# board.net
KiCad netlist of a schematic drawn in EAGLE
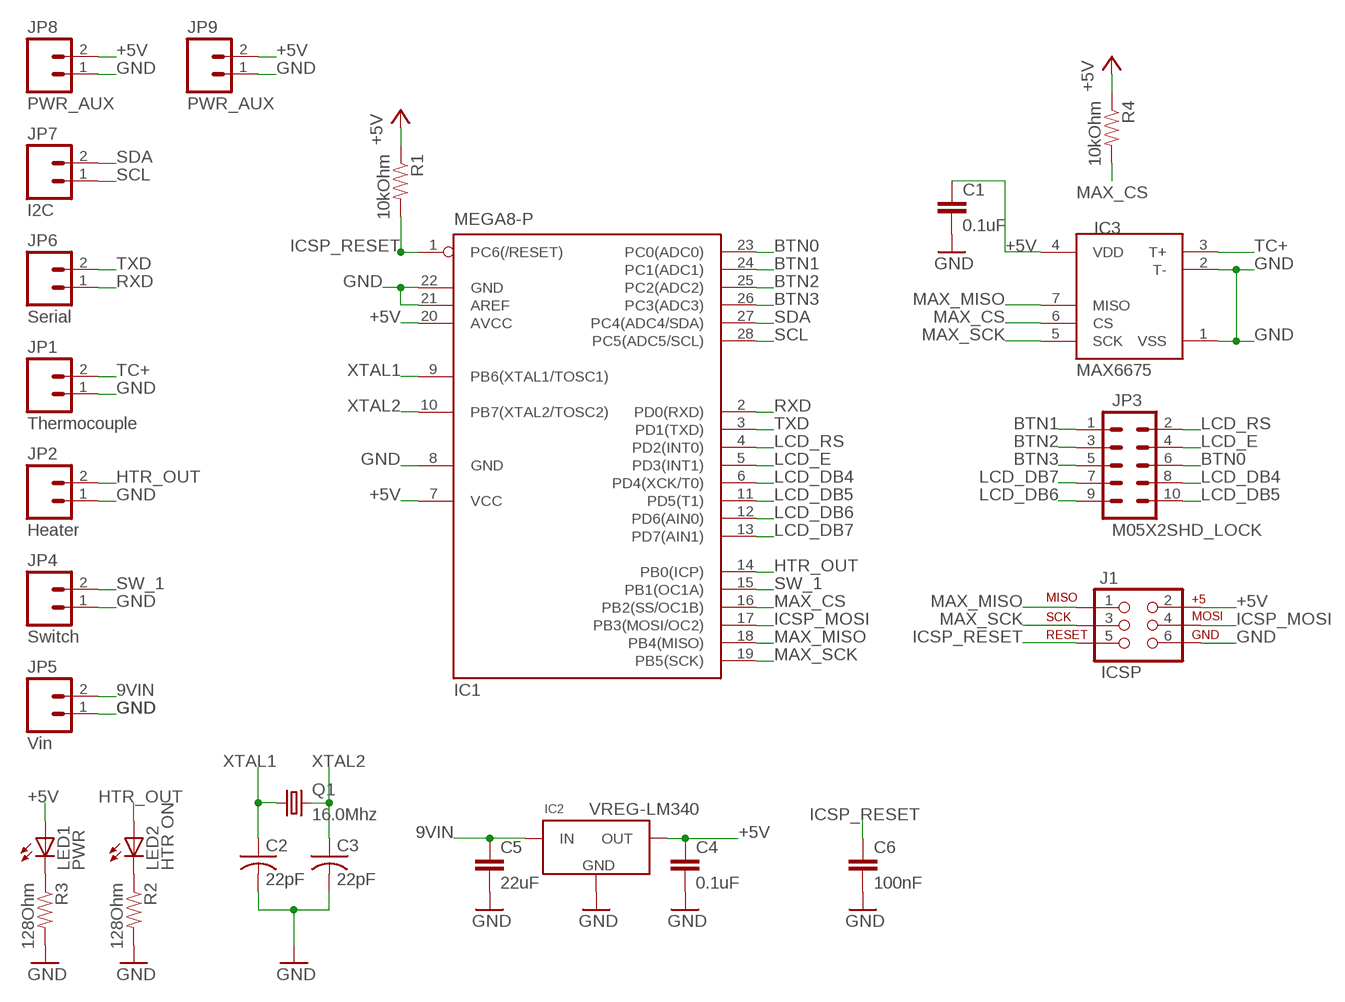
[diagram p0: schematic, sheet 1]

(export (version "E")
  (design (tool "Eeschema 10.0.6"))
  (components
    (comp (ref "C1")
      (value "0.1uF")
      (footprint "eagle-import:CAP-PTH-SMALL")
      (libsource (lib "eagle-import") (part "SparkFun-Passives_CAPPTH"))
    )
    (comp (ref "C2")
      (value "22pF")
      (footprint "eagle-import:C025-030X050")
      (libsource (lib "eagle-import") (part "C-US025-030X050"))
    )
    (comp (ref "C3")
      (value "22pF")
      (footprint "eagle-import:C025-030X050")
      (libsource (lib "eagle-import") (part "C-US025-030X050"))
    )
    (comp (ref "C4")
      (value "0.1uF")
      (footprint "eagle-import:CAP-PTH-SMALL")
      (libsource (lib "eagle-import") (part "SparkFun-Passives_CAPPTH"))
    )
    (comp (ref "C5")
      (value "22uF")
      (footprint "eagle-import:CAP-PTH-5MM")
      (libsource (lib "eagle-import") (part "CAPPTH1"))
    )
    (comp (ref "C6")
      (value "100nF")
      (footprint "eagle-import:0603-CAP")
      (libsource (lib "eagle-import") (part "CAP0603-CAP"))
    )
    (comp (ref "IC1")
      (value "MEGA8-P")
      (footprint "eagle-import:DIL28-3")
      (libsource (lib "eagle-import") (part "MEGA8-P"))
    )
    (comp (ref "IC2")
      (value "VREG-LM340")
      (footprint "eagle-import:D2PACK_A")
      (libsource (lib "eagle-import") (part "VREG-LM340"))
    )
    (comp (ref "IC3")
      (value "MAX6675")
      (footprint "eagle-import:SO08-MAX6675")
      (libsource (lib "eagle-import") (part "MAX6675"))
    )
    (comp (ref "J1")
      (value "ICSP")
      (footprint "eagle-import:2X3")
      (libsource (lib "eagle-import") (part "AVR_SPI_PRG_6PTH"))
    )
    (comp (ref "JP1")
      (value "Thermocouple")
      (footprint "eagle-import:SCREWTERMINAL-5MM-2")
      (libsource (lib "eagle-import") (part "M025MM"))
    )
    (comp (ref "JP2")
      (value "Heater")
      (footprint "eagle-import:SCREWTERMINAL-5MM-2")
      (libsource (lib "eagle-import") (part "M025MM"))
    )
    (comp (ref "JP3")
      (value "M05X2SHD_LOCK")
      (footprint "eagle-import:2X5-SHROUDED_LOCK")
      (libsource (lib "eagle-import") (part "M05X2SHD_LOCK"))
    )
    (comp (ref "JP4")
      (value "Switch")
      (footprint "eagle-import:SCREWTERMINAL-5MM-2")
      (libsource (lib "eagle-import") (part "M025MM"))
    )
    (comp (ref "JP5")
      (value "Vin")
      (footprint "eagle-import:SCREWTERMINAL-5MM-2")
      (libsource (lib "eagle-import") (part "M025MM"))
    )
    (comp (ref "JP6")
      (value "Serial")
      (footprint "eagle-import:1X02")
      (libsource (lib "eagle-import") (part "M02PTH"))
    )
    (comp (ref "JP7")
      (value "I2C")
      (footprint "eagle-import:1X02")
      (libsource (lib "eagle-import") (part "M02PTH"))
    )
    (comp (ref "JP8")
      (value "PWR_AUX")
      (footprint "eagle-import:1X02")
      (libsource (lib "eagle-import") (part "M02PTH"))
    )
    (comp (ref "JP9")
      (value "PWR_AUX")
      (footprint "eagle-import:1X02")
      (libsource (lib "eagle-import") (part "M02PTH"))
    )
    (comp (ref "LED1")
      (value "PWR")
      (footprint "eagle-import:LED-0603")
      (libsource (lib "eagle-import") (part "LED-GREEN0603"))
    )
    (comp (ref "LED2")
      (value "HTR ON")
      (footprint "eagle-import:LED-0603")
      (fields (field (name "PROD_ID") "DIO-00819"))
      (libsource (lib "eagle-import") (part "LED-RED0603"))
    )
    (comp (ref "Q1")
      (value "16.0Mhz")
      (footprint "eagle-import:HC49_S")
      (libsource (lib "eagle-import") (part "CRYSTALHC49S"))
    )
    (comp (ref "R1")
      (value "10kOhm")
      (footprint "eagle-import:1206")
      (libsource (lib "eagle-import") (part "RESISTOR1206"))
    )
    (comp (ref "R2")
      (value "128Ohm")
      (footprint "eagle-import:1206")
      (libsource (lib "eagle-import") (part "RESISTOR1206"))
    )
    (comp (ref "R3")
      (value "128Ohm")
      (footprint "eagle-import:1206")
      (libsource (lib "eagle-import") (part "RESISTOR1206"))
    )
    (comp (ref "R4")
      (value "10kOhm")
      (footprint "eagle-import:1206")
      (libsource (lib "eagle-import") (part "RESISTOR1206"))
    )
  )
  (nets
    (net (code "1") (name "+5V") (class "Default")
      (node (ref "C1") (pin "1") (pinfunction "1_1") (pintype "passive"))
      (node (ref "C4") (pin "1") (pinfunction "1_1") (pintype "passive"))
      (node (ref "IC1") (pin "20") (pinfunction "AVCC_20") (pintype "power_in"))
      (node (ref "IC1") (pin "7") (pinfunction "VCC_7") (pintype "power_in"))
      (node (ref "IC2") (pin "3") (pinfunction "OUT_3") (pintype "bidirectional"))
      (node (ref "IC3") (pin "4") (pinfunction "VDD_4") (pintype "bidirectional"))
      (node (ref "J1") (pin "2") (pinfunction "2_2") (pintype "passive"))
      (node (ref "JP8") (pin "2") (pinfunction "2_2") (pintype "passive"))
      (node (ref "JP9") (pin "2") (pinfunction "2_2") (pintype "passive"))
      (node (ref "LED1") (pin "A") (pinfunction "A_A") (pintype "passive"))
      (node (ref "R1") (pin "1") (pinfunction "1_1") (pintype "passive"))
      (node (ref "R4") (pin "1") (pinfunction "1_1") (pintype "passive"))
    )
    (net (code "2") (name "/9VIN") (class "Default")
      (node (ref "C5") (pin "1") (pinfunction "1_1") (pintype "passive"))
      (node (ref "IC2") (pin "1") (pinfunction "IN_1") (pintype "bidirectional"))
      (node (ref "JP5") (pin "2") (pinfunction "2_2") (pintype "passive"))
    )
    (net (code "3") (name "/BTN0") (class "Default")
      (node (ref "IC1") (pin "23") (pinfunction "PC0(ADC0)_23") (pintype "bidirectional"))
      (node (ref "JP3") (pin "6") (pinfunction "6_6") (pintype "passive"))
    )
    (net (code "4") (name "/BTN1") (class "Default")
      (node (ref "IC1") (pin "24") (pinfunction "PC1(ADC1)_24") (pintype "bidirectional"))
      (node (ref "JP3") (pin "1") (pinfunction "1_1") (pintype "passive"))
    )
    (net (code "5") (name "/BTN2") (class "Default")
      (node (ref "IC1") (pin "25") (pinfunction "PC2(ADC2)_25") (pintype "bidirectional"))
      (node (ref "JP3") (pin "3") (pinfunction "3_3") (pintype "passive"))
    )
    (net (code "6") (name "/BTN3") (class "Default")
      (node (ref "IC1") (pin "26") (pinfunction "PC3(ADC3)_26") (pintype "bidirectional"))
      (node (ref "JP3") (pin "5") (pinfunction "5_5") (pintype "passive"))
    )
    (net (code "7") (name "/HTR_OUT") (class "Default")
      (node (ref "IC1") (pin "14") (pinfunction "PB0(ICP)_14") (pintype "bidirectional"))
      (node (ref "JP2") (pin "2") (pinfunction "2_2") (pintype "passive"))
      (node (ref "LED2") (pin "A") (pinfunction "A_A") (pintype "passive"))
    )
    (net (code "8") (name "/ICSP_MOSI") (class "Default")
      (node (ref "IC1") (pin "17") (pinfunction "PB3(MOSI/OC2)_17") (pintype "bidirectional"))
      (node (ref "J1") (pin "4") (pinfunction "4_4") (pintype "passive"))
    )
    (net (code "9") (name "/ICSP_RESET") (class "Default")
      (node (ref "C6") (pin "1") (pinfunction "1_1") (pintype "passive"))
      (node (ref "IC1") (pin "1") (pinfunction "PC6(/RESET)_1") (pintype "bidirectional"))
      (node (ref "J1") (pin "5") (pinfunction "5_5") (pintype "passive"))
      (node (ref "R1") (pin "2") (pinfunction "2_2") (pintype "passive"))
    )
    (net (code "10") (name "/LCD_DB4") (class "Default")
      (node (ref "IC1") (pin "6") (pinfunction "PD4(XCK/T0)_6") (pintype "bidirectional"))
      (node (ref "JP3") (pin "8") (pinfunction "8_8") (pintype "passive"))
    )
    (net (code "11") (name "/LCD_DB5") (class "Default")
      (node (ref "IC1") (pin "11") (pinfunction "PD5(T1)_11") (pintype "bidirectional"))
      (node (ref "JP3") (pin "10") (pinfunction "10_10") (pintype "passive"))
    )
    (net (code "12") (name "/LCD_DB6") (class "Default")
      (node (ref "IC1") (pin "12") (pinfunction "PD6(AIN0)_12") (pintype "bidirectional"))
      (node (ref "JP3") (pin "9") (pinfunction "9_9") (pintype "passive"))
    )
    (net (code "13") (name "/LCD_DB7") (class "Default")
      (node (ref "IC1") (pin "13") (pinfunction "PD7(AIN1)_13") (pintype "bidirectional"))
      (node (ref "JP3") (pin "7") (pinfunction "7_7") (pintype "passive"))
    )
    (net (code "14") (name "/LCD_E") (class "Default")
      (node (ref "IC1") (pin "5") (pinfunction "PD3(INT1)_5") (pintype "bidirectional"))
      (node (ref "JP3") (pin "4") (pinfunction "4_4") (pintype "passive"))
    )
    (net (code "15") (name "/LCD_RS") (class "Default")
      (node (ref "IC1") (pin "4") (pinfunction "PD2(INT0)_4") (pintype "bidirectional"))
      (node (ref "JP3") (pin "2") (pinfunction "2_2") (pintype "passive"))
    )
    (net (code "16") (name "/MAX_CS") (class "Default")
      (node (ref "IC1") (pin "16") (pinfunction "PB2(SS/OC1B)_16") (pintype "bidirectional"))
      (node (ref "IC3") (pin "6") (pinfunction "CS_6") (pintype "bidirectional"))
      (node (ref "R4") (pin "2") (pinfunction "2_2") (pintype "passive"))
    )
    (net (code "17") (name "/MAX_MISO") (class "Default")
      (node (ref "IC1") (pin "18") (pinfunction "PB4(MISO)_18") (pintype "bidirectional"))
      (node (ref "IC3") (pin "7") (pinfunction "MISO_7") (pintype "bidirectional"))
      (node (ref "J1") (pin "1") (pinfunction "1_1") (pintype "passive"))
    )
    (net (code "18") (name "/MAX_SCK") (class "Default")
      (node (ref "IC1") (pin "19") (pinfunction "PB5(SCK)_19") (pintype "bidirectional"))
      (node (ref "IC3") (pin "5") (pinfunction "SCK_5") (pintype "bidirectional"))
      (node (ref "J1") (pin "3") (pinfunction "3_3") (pintype "passive"))
    )
    (net (code "19") (name "/RXD") (class "Default")
      (node (ref "IC1") (pin "2") (pinfunction "PD0(RXD)_2") (pintype "bidirectional"))
      (node (ref "JP6") (pin "1") (pinfunction "1_1") (pintype "passive"))
    )
    (net (code "20") (name "/SCL") (class "Default")
      (node (ref "IC1") (pin "28") (pinfunction "PC5(ADC5/SCL)_28") (pintype "bidirectional"))
      (node (ref "JP7") (pin "1") (pinfunction "1_1") (pintype "passive"))
    )
    (net (code "21") (name "/SDA") (class "Default")
      (node (ref "IC1") (pin "27") (pinfunction "PC4(ADC4/SDA)_27") (pintype "bidirectional"))
      (node (ref "JP7") (pin "2") (pinfunction "2_2") (pintype "passive"))
    )
    (net (code "22") (name "/SW_1") (class "Default")
      (node (ref "IC1") (pin "15") (pinfunction "PB1(OC1A)_15") (pintype "bidirectional"))
      (node (ref "JP4") (pin "2") (pinfunction "2_2") (pintype "passive"))
    )
    (net (code "23") (name "/TC+") (class "Default")
      (node (ref "IC3") (pin "3") (pinfunction "T+_3") (pintype "bidirectional"))
      (node (ref "JP1") (pin "2") (pinfunction "2_2") (pintype "passive"))
    )
    (net (code "24") (name "/TXD") (class "Default")
      (node (ref "IC1") (pin "3") (pinfunction "PD1(TXD)_3") (pintype "bidirectional"))
      (node (ref "JP6") (pin "2") (pinfunction "2_2") (pintype "passive"))
    )
    (net (code "25") (name "/XTAL1") (class "Default")
      (node (ref "C2") (pin "1") (pinfunction "1_1") (pintype "passive"))
      (node (ref "IC1") (pin "9") (pinfunction "PB6(XTAL1/TOSC1)_9") (pintype "bidirectional"))
      (node (ref "Q1") (pin "1") (pinfunction "1_1") (pintype "passive"))
    )
    (net (code "26") (name "/XTAL2") (class "Default")
      (node (ref "C3") (pin "1") (pinfunction "1_1") (pintype "passive"))
      (node (ref "IC1") (pin "10") (pinfunction "PB7(XTAL2/TOSC2)_10") (pintype "bidirectional"))
      (node (ref "Q1") (pin "2") (pinfunction "2_2") (pintype "passive"))
    )
    (net (code "27") (name "GND") (class "Default")
      (node (ref "C1") (pin "2") (pinfunction "2_2") (pintype "passive"))
      (node (ref "C2") (pin "2") (pinfunction "2_2") (pintype "passive"))
      (node (ref "C3") (pin "2") (pinfunction "2_2") (pintype "passive"))
      (node (ref "C4") (pin "2") (pinfunction "2_2") (pintype "passive"))
      (node (ref "C5") (pin "2") (pinfunction "2_2") (pintype "passive"))
      (node (ref "C6") (pin "2") (pinfunction "2_2") (pintype "passive"))
      (node (ref "IC1") (pin "21") (pinfunction "AREF_21") (pintype "passive"))
      (node (ref "IC1") (pin "22") (pinfunction "GND_22") (pintype "power_in"))
      (node (ref "IC1") (pin "8") (pinfunction "GND_8") (pintype "power_in"))
      (node (ref "IC2") (pin "2") (pinfunction "GND_2") (pintype "bidirectional"))
      (node (ref "IC2") (pin "TAB") (pinfunction "GND_TAB") (pintype "bidirectional"))
      (node (ref "IC3") (pin "1") (pinfunction "VSS_1") (pintype "bidirectional"))
      (node (ref "IC3") (pin "2") (pinfunction "T-_2") (pintype "bidirectional"))
      (node (ref "J1") (pin "6") (pinfunction "6_6") (pintype "passive"))
      (node (ref "JP1") (pin "1") (pinfunction "1_1") (pintype "passive"))
      (node (ref "JP2") (pin "1") (pinfunction "1_1") (pintype "passive"))
      (node (ref "JP4") (pin "1") (pinfunction "1_1") (pintype "passive"))
      (node (ref "JP5") (pin "1") (pinfunction "1_1") (pintype "passive"))
      (node (ref "JP8") (pin "1") (pinfunction "1_1") (pintype "passive"))
      (node (ref "JP9") (pin "1") (pinfunction "1_1") (pintype "passive"))
      (node (ref "R2") (pin "2") (pinfunction "2_2") (pintype "passive"))
      (node (ref "R3") (pin "2") (pinfunction "2_2") (pintype "passive"))
    )
    (net (code "28") (name "Net-(LED1-PadC)") (class "Default")
      (node (ref "LED1") (pin "C") (pinfunction "C_C") (pintype "passive"))
      (node (ref "R3") (pin "1") (pinfunction "1_1") (pintype "passive"))
    )
    (net (code "29") (name "Net-(LED2-PadC)") (class "Default")
      (node (ref "LED2") (pin "C") (pinfunction "C_C") (pintype "passive"))
      (node (ref "R2") (pin "1") (pinfunction "1_1") (pintype "passive"))
    )
  )
)
